# DW3000.net
KiCad netlist of a schematic drawn in Altium Designer
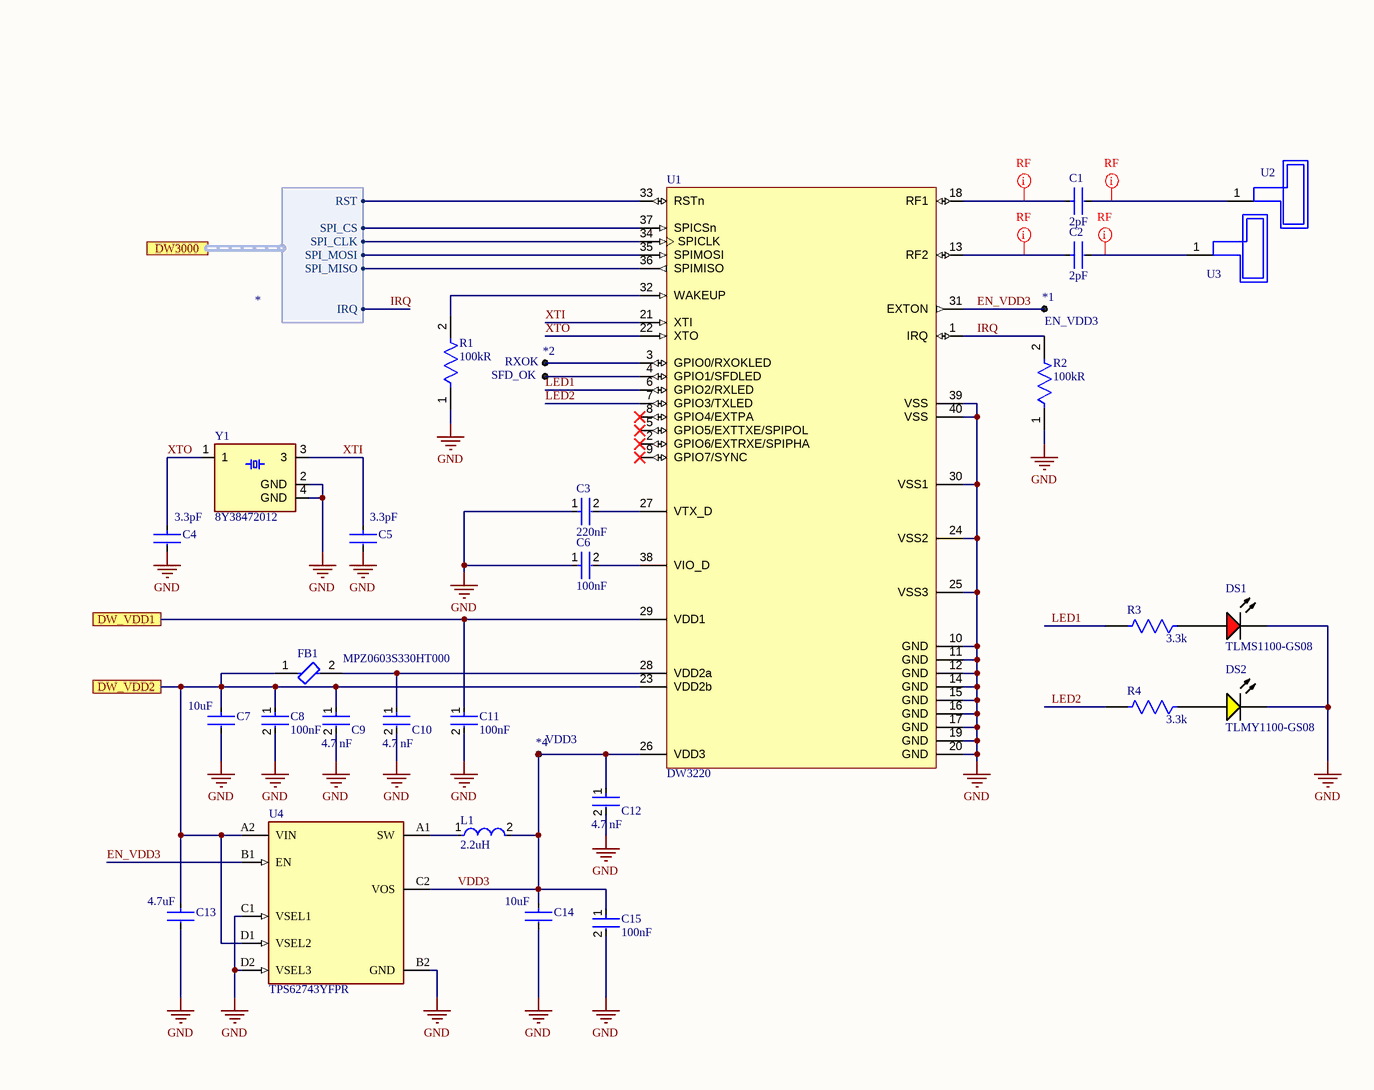
[diagram p0: DW3000.SchDoc]

(export (version "E")
  (design (tool "Eeschema 10.0.6"))
  (components
    (comp (ref "*1")
      (value "EN_VDD3")
      (footprint "Pad-0.6mm")
      (description "0.6mm SMT Test Pad")
      (libsource (lib "ETHZ Vault") (part "Test Pad"))
    )
    (comp (ref "*2")
      (value "RXOK")
      (footprint "Pad-1mm")
      (description "1mm SMT Test Pad")
      (libsource (lib "ETHZ Vault") (part "Test Pad"))
    )
    (comp (ref "*3")
      (value "SFD_OK")
      (footprint "Pad-1mm")
      (description "1mm SMT Test Pad")
      (libsource (lib "ETHZ Vault") (part "Test Pad"))
    )
    (comp (ref "*4")
      (value "VDD3")
      (footprint "Pad-0.6mm")
      (description "0.6mm SMT Test Pad")
      (libsource (lib "ETHZ Vault") (part "Test Pad"))
    )
    (comp (ref "C1")
      (value "GJM0335C1E2R0WB01D")
      (footprint "FP-GJM033-0_03-IPC_B")
      (description "Ceramic Capacitor 2pF ±0.05pF 25V C0G 0201 (0603 Metric)")
      (fields (field (name "CAPACITANCE") "2pF"))
      (libsource (lib "") (part "b4654b650e69147ec39a6b967a45e02_1"))
    )
    (comp (ref "C2")
      (value "GJM0335C1E2R0WB01D")
      (footprint "FP-GJM033-0_03-IPC_B")
      (description "Ceramic Capacitor 2pF ±0.05pF 25V C0G 0201 (0603 Metric)")
      (fields (field (name "CAPACITANCE") "2pF"))
      (libsource (lib "") (part "b4654b650e69147ec39a6b967a45e02_1"))
    )
    (comp (ref "C3")
      (value "GRM155R71C224KA12D")
      (footprint "FP-GRM155-0_05-IPC_C")
      (description "Chip Multilayer Ceramic Capacitors for General Purpose, 0402, 0.22uF, X7R, 15%, 10%, 16V")
      (fields
        (field (name "CAPACITANCE") "220nF")
        (field (name "VOLTAGE") "16V")
        (field (name "TOLERANCE") "10%")
      )
      (libsource (lib "Altium Content Vault") (part "02cd4be3c70576c341d710602a673aa"))
    )
    (comp (ref "C4")
      (value "GJM1555C1H3R3BB01D")
      (footprint "FP-GJM155-0_05-IPC_C")
      (description "Multi-Layer Ceramic Capacitor 3.3pF C0G  ±0.1pF 0402 Paper T/R")
      (fields (field (name "VOLTAGE") "50V") (field (name "CAPACITANCE") "3.3pF"))
      (libsource (lib "") (part "02cd4be3c70576c341d710602a673aa_1"))
    )
    (comp (ref "C5")
      (value "GJM1555C1H3R3BB01D")
      (footprint "FP-GJM155-0_05-IPC_C")
      (description "Multi-Layer Ceramic Capacitor 3.3pF C0G  ±0.1pF 0402 Paper T/R")
      (fields (field (name "VOLTAGE") "50V") (field (name "CAPACITANCE") "3.3pF"))
      (libsource (lib "") (part "02cd4be3c70576c341d710602a673aa_1"))
    )
    (comp (ref "C6")
      (value "GRM155R71E104ME14D")
      (footprint "FP-GRM155-0_05-IPC_B")
      (description "Chip Multilayer Ceramic Capacitors for General Purpose, 0402, 0.10uF, X7R, 15%, 20%, 25V")
      (fields (field (name "TOLERANCE") "20%") (field (name "CAPACITANCE") "100nF"))
      (libsource (lib "Altium Content Vault") (part "02cd4be3c70576c341d710602a673aa"))
    )
    (comp (ref "C7")
      (value "GRM155R60J106ME47D")
      (footprint "FP-GRM155-0_2-0_1-IPC_C")
      (description "Chip Multilayer Ceramic Capacitors for General Purpose, 0402, 10uF, X5R, 15%, 20%, 6.3V")
      (fields (field (name "TOLERANCE") "20%") (field (name "CAPACITANCE") "10uF"))
      (libsource (lib "") (part "b4654b650e69147ec39a6b967a45e02_1"))
    )
    (comp (ref "C8")
      (value "GRM155R71E104ME14D")
      (footprint "FP-GRM155-0_05-IPC_B")
      (description "Chip Multilayer Ceramic Capacitors for General Purpose, 0402, 0.10uF, X7R, 15%, 20%, 25V")
      (fields (field (name "TOLERANCE") "20%") (field (name "CAPACITANCE") "100nF"))
      (libsource (lib "Altium Content Vault") (part "02cd4be3c70576c341d710602a673aa"))
    )
    (comp (ref "C9")
      (value "GRM1555C1H472GE01D")
      (footprint "FP-GRM155-0_15-IPC_B")
      (description "Chip Multilayer Ceramic Capacitors for General Purpose, 0402, 4700pF, C0G, 30ppm/°C, 2%, 50V")
      (fields (field (name "PARAMETER 1") "4.7 nF"))
      (libsource (lib "Altium Content Vault") (part "b4654b650e69147ec39a6b967a45e02"))
    )
    (comp (ref "C10")
      (value "GRM1555C1H472GE01D")
      (footprint "FP-GRM155-0_15-IPC_B")
      (description "Chip Multilayer Ceramic Capacitors for General Purpose, 0402, 4700pF, C0G, 30ppm/°C, 2%, 50V")
      (fields (field (name "PARAMETER 1") "4.7 nF"))
      (libsource (lib "Altium Content Vault") (part "b4654b650e69147ec39a6b967a45e02"))
    )
    (comp (ref "C11")
      (value "GRM155R71E104ME14D")
      (footprint "FP-GRM155-0_05-IPC_B")
      (description "Chip Multilayer Ceramic Capacitors for General Purpose, 0402, 0.10uF, X7R, 15%, 20%, 25V")
      (fields (field (name "TOLERANCE") "20%") (field (name "CAPACITANCE") "100nF"))
      (libsource (lib "Altium Content Vault") (part "02cd4be3c70576c341d710602a673aa"))
    )
    (comp (ref "C12")
      (value "GRM1555C1H472GE01D")
      (footprint "FP-GRM155-0_15-IPC_B")
      (description "Chip Multilayer Ceramic Capacitors for General Purpose, 0402, 4700pF, C0G, 30ppm/°C, 2%, 50V")
      (fields (field (name "PARAMETER 1") "4.7 nF"))
      (libsource (lib "Altium Content Vault") (part "b4654b650e69147ec39a6b967a45e02"))
    )
    (comp (ref "C13")
      (value "GRM155C80J475MEAAD")
      (footprint "FP-GRM155-0_15-IPC_B")
      (description "Chip Multilayer Ceramic Capacitors for General Purpose, 0402, 4.7uF, X6S, 22%, 20%, 6.3V")
      (fields (field (name "TOLERANCE") "20%") (field (name "CAPACITANCE") "4.7uF"))
      (libsource (lib "") (part "b4654b650e69147ec39a6b967a45e02_1"))
    )
    (comp (ref "C14")
      (value "GRM155R60J106ME47D")
      (footprint "FP-GRM155-0_2-0_1-IPC_C")
      (description "Chip Multilayer Ceramic Capacitors for General Purpose, 0402, 10uF, X5R, 15%, 20%, 6.3V")
      (fields (field (name "TOLERANCE") "20%") (field (name "CAPACITANCE") "10uF"))
      (libsource (lib "") (part "b4654b650e69147ec39a6b967a45e02_1"))
    )
    (comp (ref "C15")
      (value "GRM155R71E104ME14D")
      (footprint "FP-GRM155-0_05-IPC_B")
      (description "Chip Multilayer Ceramic Capacitors for General Purpose, 0402, 0.10uF, X7R, 15%, 20%, 25V")
      (fields (field (name "TOLERANCE") "20%") (field (name "CAPACITANCE") "100nF"))
      (libsource (lib "Altium Content Vault") (part "02cd4be3c70576c341d710602a673aa"))
    )
    (comp (ref "DS1")
      (value "TLMS1100-GS08")
      (footprint "VISH-TLMX1100_V")
      (description "LED, RED, 2.1 V, -40 to 100 degC, 2-Pin SMD (0603), RoHS, Tape and Reel")
      (fields (field (name "TOLERANCE") "5%"))
      (libsource (lib "Altium Content Vault") (part "LED-RED-AK-2"))
    )
    (comp (ref "DS2")
      (value "TLMY1100-GS08")
      (footprint "VISH-TLMX1100-2_V")
      (description "Yellow LED, 20 mA, 2.1 V, -40 to 100 degC, 2-Pin SMD (0603), RoHS, Tape and Reel")
      (libsource (lib "Altium Content Vault") (part "LED-YELLOW-AK-2"))
    )
    (comp (ref "FB1")
      (value "MPZ0603S330HT000")
      (footprint "FP-MPZ0603-IPC_B")
      (description "CHIP BEADS FOR GENERAL SIGNAL LI")
      (libsource (lib "Altium Content Vault") (part "5f30dd21d616792df468990f7003faa"))
    )
    (comp (ref "L1")
      (value "1285AS-H-2R2M=P2")
      (footprint "FP-DFE201610C-IPC_C")
      (description "Shielded Wirewound Inductor 2.2uH 20% 1200mA 0.204Ω 0806 (2016)")
      (fields (field (name "INDUCTANCE") "2.2uH") (field (name "TOLERANCE") "20%"))
      (libsource (lib "Altium Content Vault") (part "725321dda6339637d4d059423bc1c3c"))
    )
    (comp (ref "R1")
      (value "CRCW0402100KFKED")
      (footprint "FP-CRCW0402-e3-IPC_C")
      (description "RES Thick Film, 100kΩ, 1%, 0.063W, 100ppm/°C, 0402")
      (fields (field (name "RESISTANCE") "100kR") (field (name "TOLERANCE") "1%"))
      (libsource (lib "Altium Content Vault") (part "1029c3af85768c4190bb7ad29bc67b5"))
    )
    (comp (ref "R2")
      (value "CRCW0402100KFKED")
      (footprint "FP-CRCW0402-e3-IPC_C")
      (description "RES Thick Film, 100kΩ, 1%, 0.063W, 100ppm/°C, 0402")
      (fields (field (name "RESISTANCE") "100kR") (field (name "TOLERANCE") "1%"))
      (libsource (lib "Altium Content Vault") (part "1029c3af85768c4190bb7ad29bc67b5"))
    )
    (comp (ref "R3")
      (value "~")
      (footprint "FP-CRCW0402-e3-IPC_C")
      (description "RES Thick Film, 3.3kΩ, 1%, 0.063W, 100ppm/°C, 0402")
      (fields (field (name "RESISTANCE") "3.3k") (field (name "TOLERANCE") "1%"))
      (libsource (lib "") (part "1029c3af85768c4190bb7ad29bc67b5_1"))
    )
    (comp (ref "R4")
      (value "~")
      (footprint "FP-CRCW0402-e3-IPC_C")
      (description "RES Thick Film, 3.3kΩ, 1%, 0.063W, 100ppm/°C, 0402")
      (fields (field (name "RESISTANCE") "3.3k") (field (name "TOLERANCE") "1%"))
      (libsource (lib "") (part "1029c3af85768c4190bb7ad29bc67b5_1"))
    )
    (comp (ref "U1")
      (value "DW3220")
      (footprint "QFN40P500X500X40_HS-40N")
      (description "Ultra-low power Wi-Fi 802.11b/g/n, without mounted antenna")
      (fields (field (name "MANUFACTURER") "Qorvo"))
      (libsource (lib "ETHZ Vault") (part "DW3220"))
    )
    (comp (ref "U2")
      (value "AH086M555003-T")
      (footprint "AH086M")
      (description "3.5GHz, 5.6GHz WiMax™ Chip RF Antenna 3.1GHz ~ 8GHz 2.6dBi, 0.7dBi Solder Surface Mount")
      (libsource (lib "ETHZ Vault") (part "Antenna"))
    )
    (comp (ref "U3")
      (value "AH086M555003-T")
      (footprint "AH086M")
      (description "3.5GHz, 5.6GHz WiMax™ Chip RF Antenna 3.1GHz ~ 8GHz 2.6dBi, 0.7dBi Solder Surface Mount")
      (libsource (lib "ETHZ Vault") (part "Antenna"))
    )
    (comp (ref "U4")
      (value "TPS62743YFPR")
      (footprint "FP-YFP0008-C01-MFG")
      (description "IC REG BUCK PROG 300MA 8DSBGA")
      (libsource (lib "Altium Content Vault") (part "8afa53303d55f9e28cdff5b5725789a"))
    )
    (comp (ref "Y1")
      (value "8Y38472012")
      (footprint "OSCSC320X250X100N")
      (description "Crystal 38.4MHz ±10ppm (Stability) 10pF FUND 80Ohm 4-Pin Mini-CSMD T/R")
      (libsource (lib "ABM8G-14.31818MHZ-B4Y-T") (part "ABM8G-14.31818MHZ-B4Y-T"))
    )
  )
  (nets
    (net (code "2") (name "/DW_VDD1") (class "Default")
      (node (ref "C11") (pin "1") (pinfunction "1_1") (pintype "passive"))
      (node (ref "U1") (pin "29") (pinfunction "VDD1_29") (pintype "power_in"))
    )
    (net (code "3") (name "/DW_VDD2") (class "Default")
      (node (ref "C13") (pin "1") (pinfunction "1_1") (pintype "passive"))
      (node (ref "C7") (pin "1") (pinfunction "1_1") (pintype "passive"))
      (node (ref "C8") (pin "1") (pinfunction "1_1") (pintype "passive"))
      (node (ref "C9") (pin "1") (pinfunction "1_1") (pintype "passive"))
      (node (ref "FB1") (pin "1") (pinfunction "1_1") (pintype "passive"))
      (node (ref "U1") (pin "23") (pinfunction "VDD2b_23") (pintype "power_in"))
      (node (ref "U4") (pin "A2") (pinfunction "VIN_A2") (pintype "power_in"))
      (node (ref "U4") (pin "D1") (pinfunction "VSEL2_D1") (pintype "input"))
    )
    (net (code "4") (name "/EN_VDD3") (class "Default")
      (node (ref "*1") (pin "1") (pinfunction "1_1") (pintype "passive"))
      (node (ref "U1") (pin "31") (pinfunction "EXTON_31") (pintype "output"))
      (node (ref "U4") (pin "B1") (pinfunction "EN_B1") (pintype "input"))
    )
    (net (code "5") (name "/IRQ") (class "Default")
      (node (ref "R2") (pin "2") (pinfunction "2_2") (pintype "passive"))
      (node (ref "U1") (pin "1") (pinfunction "IRQ_1") (pintype "bidirectional"))
    )
    (net (code "6") (name "/LED1") (class "Default")
      (node (ref "R3") (pin "2") (pinfunction "2_2") (pintype "passive"))
      (node (ref "U1") (pin "6") (pinfunction "GPIO2/RXLED_6") (pintype "bidirectional"))
    )
    (net (code "7") (name "/LED2") (class "Default")
      (node (ref "R4") (pin "2") (pinfunction "2_2") (pintype "passive"))
      (node (ref "U1") (pin "7") (pinfunction "GPIO3/TXLED_7") (pintype "bidirectional"))
    )
    (net (code "8") (name "/RST") (class "Default")
      (node (ref "U1") (pin "33") (pinfunction "RSTn_33") (pintype "bidirectional"))
    )
    (net (code "9") (name "/SPI_CLK") (class "Default")
      (node (ref "U1") (pin "34") (pinfunction "SPICLK_34") (pintype "input"))
    )
    (net (code "10") (name "/SPI_CS") (class "Default")
      (node (ref "U1") (pin "37") (pinfunction "SPICSn_37") (pintype "input"))
    )
    (net (code "11") (name "/SPI_MISO") (class "Default")
      (node (ref "U1") (pin "36") (pinfunction "SPIMISO_36") (pintype "output"))
    )
    (net (code "12") (name "/SPI_MOSI") (class "Default")
      (node (ref "U1") (pin "35") (pinfunction "SPIMOSI_35") (pintype "input"))
    )
    (net (code "13") (name "/VDD3") (class "Default")
      (node (ref "*4") (pin "1") (pinfunction "1_1") (pintype "passive"))
      (node (ref "C12") (pin "1") (pinfunction "1_1") (pintype "passive"))
      (node (ref "C14") (pin "1") (pinfunction "1_1") (pintype "passive"))
      (node (ref "C15") (pin "1") (pinfunction "1_1") (pintype "passive"))
      (node (ref "L1") (pin "2") (pinfunction "2_2") (pintype "passive"))
      (node (ref "U1") (pin "26") (pinfunction "VDD3_26") (pintype "power_in"))
      (node (ref "U4") (pin "C2") (pinfunction "VOS_C2") (pintype "passive"))
    )
    (net (code "14") (name "/XTI") (class "Default")
      (node (ref "C5") (pin "1") (pinfunction "1_1") (pintype "passive"))
      (node (ref "U1") (pin "21") (pinfunction "XTI_21") (pintype "input"))
      (node (ref "Y1") (pin "3") (pinfunction "3_3") (pintype "passive"))
    )
    (net (code "15") (name "/XTO") (class "Default")
      (node (ref "C4") (pin "1") (pinfunction "1_1") (pintype "passive"))
      (node (ref "U1") (pin "22") (pinfunction "XTO_22") (pintype "input"))
      (node (ref "Y1") (pin "1") (pinfunction "1_1") (pintype "passive"))
    )
    (net (code "17") (name "GND") (class "Default")
      (node (ref "C10") (pin "2") (pinfunction "2_2") (pintype "passive"))
      (node (ref "C11") (pin "2") (pinfunction "2_2") (pintype "passive"))
      (node (ref "C12") (pin "2") (pinfunction "2_2") (pintype "passive"))
      (node (ref "C13") (pin "2") (pinfunction "2_2") (pintype "passive"))
      (node (ref "C14") (pin "2") (pinfunction "2_2") (pintype "passive"))
      (node (ref "C15") (pin "2") (pinfunction "2_2") (pintype "passive"))
      (node (ref "C3") (pin "1") (pinfunction "1_1") (pintype "passive"))
      (node (ref "C4") (pin "2") (pinfunction "2_2") (pintype "passive"))
      (node (ref "C5") (pin "2") (pinfunction "2_2") (pintype "passive"))
      (node (ref "C6") (pin "1") (pinfunction "1_1") (pintype "passive"))
      (node (ref "C7") (pin "2") (pinfunction "2_2") (pintype "passive"))
      (node (ref "C8") (pin "2") (pinfunction "2_2") (pintype "passive"))
      (node (ref "C9") (pin "2") (pinfunction "2_2") (pintype "passive"))
      (node (ref "DS1") (pin "2") (pinfunction "K_2") (pintype "passive"))
      (node (ref "DS2") (pin "2") (pinfunction "K_2") (pintype "passive"))
      (node (ref "R1") (pin "1") (pinfunction "1_1") (pintype "passive"))
      (node (ref "R2") (pin "1") (pinfunction "1_1") (pintype "passive"))
      (node (ref "U1") (pin "10") (pinfunction "GND_10") (pintype "power_in"))
      (node (ref "U1") (pin "11") (pinfunction "GND_11") (pintype "power_in"))
      (node (ref "U1") (pin "12") (pinfunction "GND_12") (pintype "power_in"))
      (node (ref "U1") (pin "14") (pinfunction "GND_14") (pintype "power_in"))
      (node (ref "U1") (pin "15") (pinfunction "GND_15") (pintype "power_in"))
      (node (ref "U1") (pin "16") (pinfunction "GND_16") (pintype "power_in"))
      (node (ref "U1") (pin "17") (pinfunction "GND_17") (pintype "power_in"))
      (node (ref "U1") (pin "19") (pinfunction "GND_19") (pintype "power_in"))
      (node (ref "U1") (pin "20") (pinfunction "GND_20") (pintype "power_in"))
      (node (ref "U1") (pin "24") (pinfunction "VSS2_24") (pintype "power_in"))
      (node (ref "U1") (pin "25") (pinfunction "VSS3_25") (pintype "power_in"))
      (node (ref "U1") (pin "30") (pinfunction "VSS1_30") (pintype "power_in"))
      (node (ref "U1") (pin "39") (pinfunction "VSS_39") (pintype "power_in"))
      (node (ref "U1") (pin "40") (pinfunction "VSS_40") (pintype "power_in"))
      (node (ref "U4") (pin "B2") (pinfunction "GND_B2") (pintype "power_in"))
      (node (ref "U4") (pin "C1") (pinfunction "VSEL1_C1") (pintype "input"))
      (node (ref "U4") (pin "D2") (pinfunction "VSEL3_D2") (pintype "input"))
      (node (ref "Y1") (pin "2") (pinfunction "GND_2") (pintype "power_in"))
      (node (ref "Y1") (pin "4") (pinfunction "GND_4") (pintype "power_in"))
    )
    (net (code "18") (name "Net-(C1-Pad2)") (class "Default")
      (node (ref "C1") (pin "2") (pinfunction "2_2") (pintype "passive"))
      (node (ref "U2") (pin "1") (pinfunction "1_1") (pintype "passive"))
    )
    (net (code "19") (name "Net-(C2-Pad2)") (class "Default")
      (node (ref "C2") (pin "2") (pinfunction "2_2") (pintype "passive"))
      (node (ref "U3") (pin "1") (pinfunction "1_1") (pintype "passive"))
    )
    (net (code "20") (name "Net-(DS1-A)") (class "Default")
      (node (ref "DS1") (pin "1") (pinfunction "A_1") (pintype "passive"))
      (node (ref "R3") (pin "1") (pinfunction "1_1") (pintype "passive"))
    )
    (net (code "21") (name "Net-(DS2-A)") (class "Default")
      (node (ref "DS2") (pin "1") (pinfunction "A_1") (pintype "passive"))
      (node (ref "R4") (pin "1") (pinfunction "1_1") (pintype "passive"))
    )
    (net (code "22") (name "Net-(U1-GPIO0{slash}RXOKLED)") (class "Default")
      (node (ref "*2") (pin "1") (pinfunction "1_1") (pintype "passive"))
      (node (ref "U1") (pin "3") (pinfunction "GPIO0/RXOKLED_3") (pintype "bidirectional"))
    )
    (net (code "23") (name "Net-(U1-GPIO1{slash}SFDLED)") (class "Default")
      (node (ref "*3") (pin "1") (pinfunction "1_1") (pintype "passive"))
      (node (ref "U1") (pin "4") (pinfunction "GPIO1/SFDLED_4") (pintype "bidirectional"))
    )
    (net (code "24") (name "Net-(U1-RF1)") (class "Default")
      (node (ref "C1") (pin "1") (pinfunction "1_1") (pintype "passive"))
      (node (ref "U1") (pin "18") (pinfunction "RF1_18") (pintype "bidirectional"))
    )
    (net (code "25") (name "Net-(U1-RF2)") (class "Default")
      (node (ref "C2") (pin "1") (pinfunction "1_1") (pintype "passive"))
      (node (ref "U1") (pin "13") (pinfunction "RF2_13") (pintype "bidirectional"))
    )
    (net (code "26") (name "Net-(U1-VDD2a)") (class "Default")
      (node (ref "C10") (pin "1") (pinfunction "1_1") (pintype "passive"))
      (node (ref "FB1") (pin "2") (pinfunction "2_2") (pintype "passive"))
      (node (ref "U1") (pin "28") (pinfunction "VDD2a_28") (pintype "power_in"))
    )
    (net (code "27") (name "Net-(U1-VIO_D)") (class "Default")
      (node (ref "C6") (pin "2") (pinfunction "2_2") (pintype "passive"))
      (node (ref "U1") (pin "38") (pinfunction "VIO_D_38") (pintype "passive"))
    )
    (net (code "28") (name "Net-(U1-VTX_D)") (class "Default")
      (node (ref "C3") (pin "2") (pinfunction "2_2") (pintype "passive"))
      (node (ref "U1") (pin "27") (pinfunction "VTX_D_27") (pintype "passive"))
    )
    (net (code "29") (name "Net-(U1-WAKEUP)") (class "Default")
      (node (ref "R1") (pin "2") (pinfunction "2_2") (pintype "passive"))
      (node (ref "U1") (pin "32") (pinfunction "WAKEUP_32") (pintype "input"))
    )
    (net (code "30") (name "Net-(U4-SW)") (class "Default")
      (node (ref "L1") (pin "1") (pinfunction "1_1") (pintype "passive"))
      (node (ref "U4") (pin "A1") (pinfunction "SW_A1") (pintype "passive"))
    )
    (net (code "31") (name "unconnected-(U1-GPIO4{slash}EXTPA-Pad8)") (class "Default")
      (node (ref "U1") (pin "8") (pinfunction "GPIO4/EXTPA_8") (pintype "bidirectional+no_connect"))
    )
    (net (code "32") (name "unconnected-(U1-GPIO5{slash}EXTTXE{slash}SPIPOL-Pad5)") (class "Default")
      (node (ref "U1") (pin "5") (pinfunction "GPIO5/EXTTXE/SPIPOL_5") (pintype "bidirectional+no_connect"))
    )
    (net (code "33") (name "unconnected-(U1-GPIO6{slash}EXTRXE{slash}SPIPHA-Pad2)") (class "Default")
      (node (ref "U1") (pin "2") (pinfunction "GPIO6/EXTRXE/SPIPHA_2") (pintype "bidirectional+no_connect"))
    )
    (net (code "34") (name "unconnected-(U1-GPIO7{slash}SYNC-Pad9)") (class "Default")
      (node (ref "U1") (pin "9") (pinfunction "GPIO7/SYNC_9") (pintype "bidirectional+no_connect"))
    )
  )
)
